# pinguino_p8b3_RC2.net
KiCad netlist of a schematic drawn in EAGLE
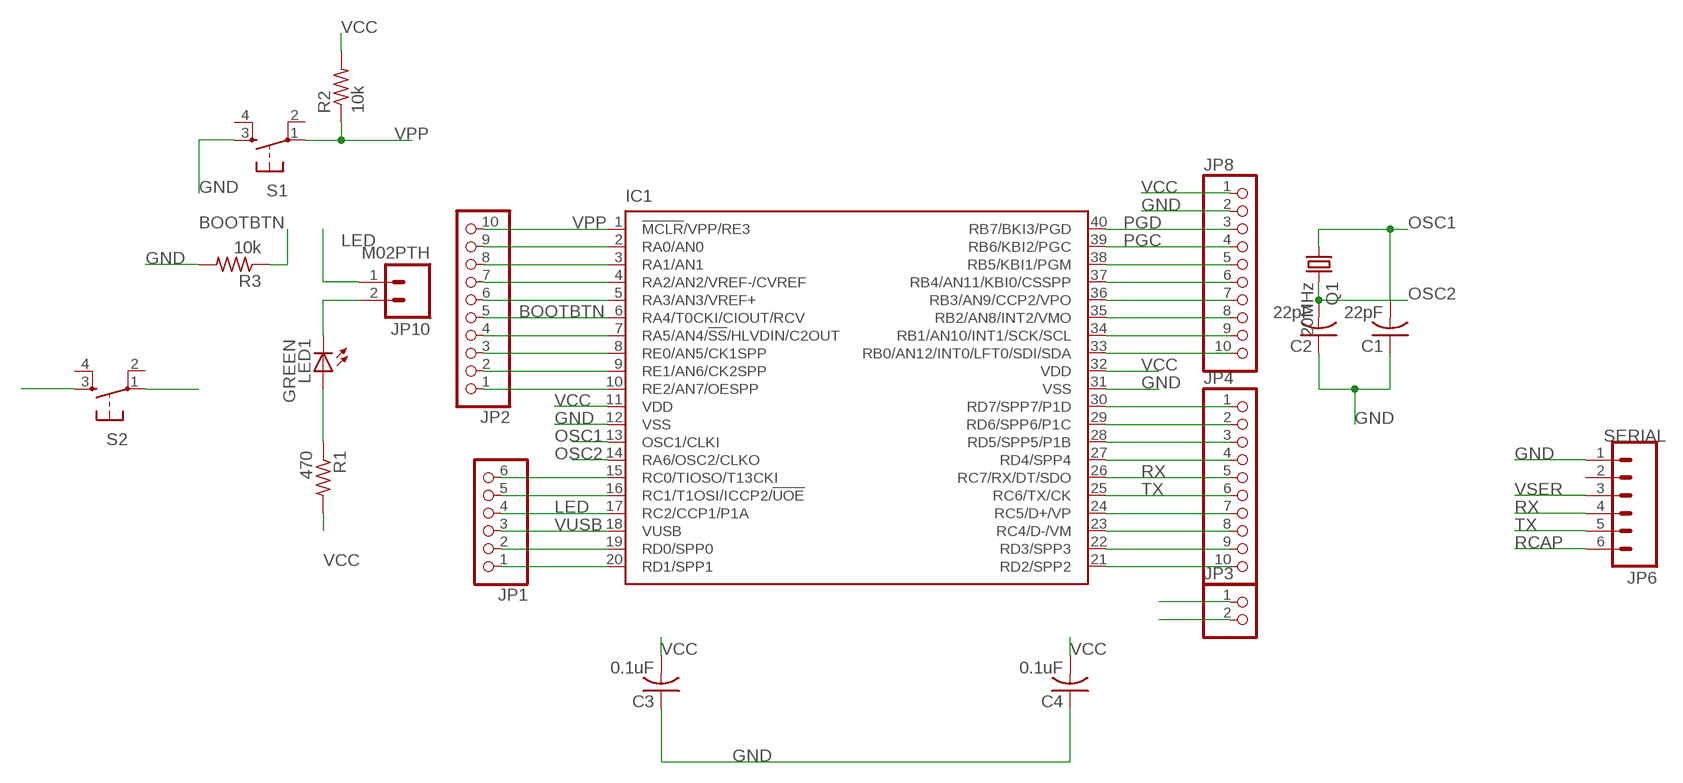
[diagram p0: schematic, sheet 1]

(export (version "E")
  (design (tool "Eeschema 10.0.6"))
  (components
    (comp (ref "C1")
      (value "22pF")
      (footprint "eagle-import:C025-025X050")
      (libsource (lib "eagle-import") (part "C-US025-025X050"))
    )
    (comp (ref "C2")
      (value "22pF")
      (footprint "eagle-import:C025-025X050")
      (libsource (lib "eagle-import") (part "C-US025-025X050"))
    )
    (comp (ref "C3")
      (value "0.1uF")
      (footprint "eagle-import:C025-025X050")
      (libsource (lib "eagle-import") (part "C-US025-025X050"))
    )
    (comp (ref "C4")
      (value "0.1uF")
      (footprint "eagle-import:C025-025X050")
      (libsource (lib "eagle-import") (part "C-US025-025X050"))
    )
    (comp (ref "IC1")
      (value "PIC18F4550_40")
      (footprint "eagle-import:DIL40")
      (libsource (lib "eagle-import") (part "PIC18F4_40550"))
    )
    (comp (ref "JP1")
      (value "PINHD-1X6")
      (footprint "eagle-import:1X06")
      (libsource (lib "eagle-import") (part "PINHD-1X6"))
    )
    (comp (ref "JP2")
      (value "PINHD-1X10")
      (footprint "eagle-import:1X10")
      (libsource (lib "eagle-import") (part "PINHD-1X10"))
    )
    (comp (ref "JP3")
      (value "PINHD-1X2")
      (footprint "eagle-import:1X02")
      (libsource (lib "eagle-import") (part "PINHD-1X2"))
    )
    (comp (ref "JP4")
      (value "PINHD-1X10")
      (footprint "eagle-import:1X10")
      (libsource (lib "eagle-import") (part "PINHD-1X10"))
    )
    (comp (ref "JP6")
      (value "M06SIP")
      (footprint "eagle-import:1X06")
      (libsource (lib "eagle-import") (part "M06SIP"))
    )
    (comp (ref "JP8")
      (value "PINHD-1X10")
      (footprint "eagle-import:1X10")
      (libsource (lib "eagle-import") (part "PINHD-1X10"))
    )
    (comp (ref "JP10")
      (value "M02PTH")
      (footprint "eagle-import:1X02")
      (libsource (lib "eagle-import") (part "M02PTH"))
    )
    (comp (ref "LED1")
      (value "GREEN")
      (footprint "eagle-import:LED3MM")
      (libsource (lib "eagle-import") (part "LED3MM"))
    )
    (comp (ref "Q1")
      (value "20MHz")
      (footprint "eagle-import:HC49US")
      (libsource (lib "eagle-import") (part "CRYSTALHC49US"))
    )
    (comp (ref "R1")
      (value "470")
      (footprint "eagle-import:0207_10")
      (libsource (lib "eagle-import") (part "R-US_0207/10"))
    )
    (comp (ref "R2")
      (value "10k")
      (footprint "eagle-import:0207_7")
      (libsource (lib "eagle-import") (part "R-US_0207/7"))
    )
    (comp (ref "R3")
      (value "10k")
      (footprint "eagle-import:0207_7")
      (libsource (lib "eagle-import") (part "R-US_0207/7"))
    )
    (comp (ref "S1")
      (value "TAC_SWITCHPTH")
      (footprint "eagle-import:TACTILE-PTH")
      (libsource (lib "eagle-import") (part "TAC_SWITCHPTH"))
    )
    (comp (ref "S2")
      (value "TAC_SWITCHPTH")
      (footprint "eagle-import:TACTILE-PTH")
      (libsource (lib "eagle-import") (part "TAC_SWITCHPTH"))
    )
  )
  (nets
    (net (code "1") (name "/BOOTBTN") (class "Default")
      (node (ref "IC1") (pin "6") (pinfunction "RA4/T0CKI/CIOUT/RCV_6") (pintype "bidirectional"))
      (node (ref "JP2") (pin "5") (pinfunction "5_5") (pintype "passive"))
      (node (ref "R3") (pin "1") (pinfunction "1_1") (pintype "passive"))
      (node (ref "S2") (pin "1") (pinfunction "1_1") (pintype "passive"))
    )
    (net (code "2") (name "/GND") (class "Default")
      (node (ref "C1") (pin "1") (pinfunction "1_1") (pintype "passive"))
      (node (ref "C2") (pin "1") (pinfunction "1_1") (pintype "passive"))
      (node (ref "C3") (pin "1") (pinfunction "1_1") (pintype "passive"))
      (node (ref "C4") (pin "1") (pinfunction "1_1") (pintype "passive"))
      (node (ref "IC1") (pin "12") (pinfunction "VSS_12") (pintype "power_in"))
      (node (ref "IC1") (pin "31") (pinfunction "VSS_31") (pintype "power_in"))
      (node (ref "JP6") (pin "1") (pinfunction "1_1") (pintype "passive"))
      (node (ref "JP8") (pin "2") (pinfunction "2_2") (pintype "passive"))
      (node (ref "R3") (pin "2") (pinfunction "2_2") (pintype "passive"))
      (node (ref "S1") (pin "3") (pinfunction "3_3") (pintype "passive"))
    )
    (net (code "3") (name "/LED") (class "Default")
      (node (ref "IC1") (pin "17") (pinfunction "RC2/CCP1/P1A_17") (pintype "bidirectional"))
      (node (ref "JP1") (pin "4") (pinfunction "4_4") (pintype "passive"))
      (node (ref "JP10") (pin "1") (pinfunction "1_1") (pintype "passive"))
    )
    (net (code "4") (name "/OSC1") (class "Default")
      (node (ref "C1") (pin "2") (pinfunction "2_2") (pintype "passive"))
      (node (ref "IC1") (pin "13") (pinfunction "OSC1/CLKI_13") (pintype "input"))
      (node (ref "Q1") (pin "1") (pinfunction "1_1") (pintype "passive"))
    )
    (net (code "5") (name "/OSC2") (class "Default")
      (node (ref "C2") (pin "2") (pinfunction "2_2") (pintype "passive"))
      (node (ref "IC1") (pin "14") (pinfunction "RA6/OSC2/CLKO_14") (pintype "output"))
      (node (ref "Q1") (pin "2") (pinfunction "2_2") (pintype "passive"))
    )
    (net (code "6") (name "/PGC") (class "Default")
      (node (ref "IC1") (pin "39") (pinfunction "RB6/KBI2/PGC_39") (pintype "bidirectional"))
      (node (ref "JP8") (pin "4") (pinfunction "4_4") (pintype "passive"))
    )
    (net (code "7") (name "/PGD") (class "Default")
      (node (ref "IC1") (pin "40") (pinfunction "RB7/BKI3/PGD_40") (pintype "bidirectional"))
      (node (ref "JP8") (pin "3") (pinfunction "3_3") (pintype "passive"))
    )
    (net (code "8") (name "/RCAP") (class "Default")
      (node (ref "JP6") (pin "6") (pinfunction "6_6") (pintype "passive"))
    )
    (net (code "9") (name "/RX") (class "Default")
      (node (ref "IC1") (pin "26") (pinfunction "RC7/RX/DT/SDO_26") (pintype "bidirectional"))
      (node (ref "JP4") (pin "5") (pinfunction "5_5") (pintype "passive"))
      (node (ref "JP6") (pin "4") (pinfunction "4_4") (pintype "passive"))
    )
    (net (code "10") (name "/TX") (class "Default")
      (node (ref "IC1") (pin "25") (pinfunction "RC6/TX/CK_25") (pintype "bidirectional"))
      (node (ref "JP4") (pin "6") (pinfunction "6_6") (pintype "passive"))
      (node (ref "JP6") (pin "5") (pinfunction "5_5") (pintype "passive"))
    )
    (net (code "11") (name "/VCC") (class "Default")
      (node (ref "C3") (pin "2") (pinfunction "2_2") (pintype "passive"))
      (node (ref "C4") (pin "2") (pinfunction "2_2") (pintype "passive"))
      (node (ref "IC1") (pin "11") (pinfunction "VDD_11") (pintype "power_in"))
      (node (ref "IC1") (pin "32") (pinfunction "VDD_32") (pintype "power_in"))
      (node (ref "JP3") (pin "1") (pinfunction "1_1") (pintype "passive"))
      (node (ref "JP8") (pin "1") (pinfunction "1_1") (pintype "passive"))
      (node (ref "R1") (pin "2") (pinfunction "2_2") (pintype "passive"))
      (node (ref "R2") (pin "2") (pinfunction "2_2") (pintype "passive"))
      (node (ref "S2") (pin "3") (pinfunction "3_3") (pintype "passive"))
    )
    (net (code "12") (name "/VPP") (class "Default")
      (node (ref "IC1") (pin "1") (pinfunction "~{MCLR}/VPP/RE3_1") (pintype "input"))
      (node (ref "JP2") (pin "10") (pinfunction "10_10") (pintype "passive"))
      (node (ref "R2") (pin "1") (pinfunction "1_1") (pintype "passive"))
      (node (ref "S1") (pin "1") (pinfunction "1_1") (pintype "passive"))
    )
    (net (code "13") (name "/VSER") (class "Default")
      (node (ref "JP3") (pin "2") (pinfunction "2_2") (pintype "passive"))
      (node (ref "JP6") (pin "3") (pinfunction "3_3") (pintype "passive"))
    )
    (net (code "14") (name "/VUSB") (class "Default")
      (node (ref "IC1") (pin "18") (pinfunction "VUSB_18") (pintype "bidirectional"))
      (node (ref "JP1") (pin "3") (pinfunction "3_3") (pintype "passive"))
    )
    (net (code "15") (name "Net-(IC1-RA0{slash}AN0)") (class "Default")
      (node (ref "IC1") (pin "2") (pinfunction "RA0/AN0_2") (pintype "bidirectional"))
      (node (ref "JP2") (pin "9") (pinfunction "9_9") (pintype "passive"))
    )
    (net (code "16") (name "Net-(IC1-RA1{slash}AN1)") (class "Default")
      (node (ref "IC1") (pin "3") (pinfunction "RA1/AN1_3") (pintype "bidirectional"))
      (node (ref "JP2") (pin "8") (pinfunction "8_8") (pintype "passive"))
    )
    (net (code "17") (name "Net-(IC1-RA2{slash}AN2{slash}VREF-{slash}CVREF)") (class "Default")
      (node (ref "IC1") (pin "4") (pinfunction "RA2/AN2/VREF-/CVREF_4") (pintype "bidirectional"))
      (node (ref "JP2") (pin "7") (pinfunction "7_7") (pintype "passive"))
    )
    (net (code "18") (name "Net-(IC1-RA3{slash}AN3{slash}VREF+)") (class "Default")
      (node (ref "IC1") (pin "5") (pinfunction "RA3/AN3/VREF+_5") (pintype "bidirectional"))
      (node (ref "JP2") (pin "6") (pinfunction "6_6") (pintype "passive"))
    )
    (net (code "19") (name "Net-(IC1-RA5{slash}AN4{slash}~{SS}{slash}HLVDIN{slash}C2OUT)") (class "Default")
      (node (ref "IC1") (pin "7") (pinfunction "RA5/AN4/~{SS}/HLVDIN/C2OUT_7") (pintype "bidirectional"))
      (node (ref "JP2") (pin "4") (pinfunction "4_4") (pintype "passive"))
    )
    (net (code "20") (name "Net-(IC1-RB0{slash}AN12{slash}INT0{slash}LFT0{slash}SDI{slash}SDA)") (class "Default")
      (node (ref "IC1") (pin "33") (pinfunction "RB0/AN12/INT0/LFT0/SDI/SDA_33") (pintype "bidirectional"))
      (node (ref "JP8") (pin "10") (pinfunction "10_10") (pintype "passive"))
    )
    (net (code "21") (name "Net-(IC1-RB1{slash}AN10{slash}INT1{slash}SCK{slash}SCL)") (class "Default")
      (node (ref "IC1") (pin "34") (pinfunction "RB1/AN10/INT1/SCK/SCL_34") (pintype "bidirectional"))
      (node (ref "JP8") (pin "9") (pinfunction "9_9") (pintype "passive"))
    )
    (net (code "22") (name "Net-(IC1-RB2{slash}AN8{slash}INT2{slash}VMO)") (class "Default")
      (node (ref "IC1") (pin "35") (pinfunction "RB2/AN8/INT2/VMO_35") (pintype "bidirectional"))
      (node (ref "JP8") (pin "8") (pinfunction "8_8") (pintype "passive"))
    )
    (net (code "23") (name "Net-(IC1-RB3{slash}AN9{slash}CCP2{slash}VPO)") (class "Default")
      (node (ref "IC1") (pin "36") (pinfunction "RB3/AN9/CCP2/VPO_36") (pintype "bidirectional"))
      (node (ref "JP8") (pin "7") (pinfunction "7_7") (pintype "passive"))
    )
    (net (code "24") (name "Net-(IC1-RB4{slash}AN11{slash}KBI0{slash}CSSPP)") (class "Default")
      (node (ref "IC1") (pin "37") (pinfunction "RB4/AN11/KBI0/CSSPP_37") (pintype "bidirectional"))
      (node (ref "JP8") (pin "6") (pinfunction "6_6") (pintype "passive"))
    )
    (net (code "25") (name "Net-(IC1-RB5{slash}KBI1{slash}PGM)") (class "Default")
      (node (ref "IC1") (pin "38") (pinfunction "RB5/KBI1/PGM_38") (pintype "bidirectional"))
      (node (ref "JP8") (pin "5") (pinfunction "5_5") (pintype "passive"))
    )
    (net (code "26") (name "Net-(IC1-RC0{slash}TIOSO{slash}T13CKI)") (class "Default")
      (node (ref "IC1") (pin "15") (pinfunction "RC0/TIOSO/T13CKI_15") (pintype "bidirectional"))
      (node (ref "JP1") (pin "6") (pinfunction "6_6") (pintype "passive"))
    )
    (net (code "27") (name "Net-(IC1-RC1{slash}T1OSI{slash}ICCP2{slash}~{UOE})") (class "Default")
      (node (ref "IC1") (pin "16") (pinfunction "RC1/T1OSI/ICCP2/~{UOE}_16") (pintype "bidirectional"))
      (node (ref "JP1") (pin "5") (pinfunction "5_5") (pintype "passive"))
    )
    (net (code "28") (name "Net-(IC1-RC4{slash}D-{slash}VM)") (class "Default")
      (node (ref "IC1") (pin "23") (pinfunction "RC4/D-/VM_23") (pintype "bidirectional"))
      (node (ref "JP4") (pin "8") (pinfunction "8_8") (pintype "passive"))
    )
    (net (code "29") (name "Net-(IC1-RC5{slash}D+{slash}VP)") (class "Default")
      (node (ref "IC1") (pin "24") (pinfunction "RC5/D+/VP_24") (pintype "bidirectional"))
      (node (ref "JP4") (pin "7") (pinfunction "7_7") (pintype "passive"))
    )
    (net (code "30") (name "Net-(IC1-RD0{slash}SPP0)") (class "Default")
      (node (ref "IC1") (pin "19") (pinfunction "RD0/SPP0_19") (pintype "bidirectional"))
      (node (ref "JP1") (pin "2") (pinfunction "2_2") (pintype "passive"))
    )
    (net (code "31") (name "Net-(IC1-RD1{slash}SPP1)") (class "Default")
      (node (ref "IC1") (pin "20") (pinfunction "RD1/SPP1_20") (pintype "bidirectional"))
      (node (ref "JP1") (pin "1") (pinfunction "1_1") (pintype "passive"))
    )
    (net (code "32") (name "Net-(IC1-RD2{slash}SPP2)") (class "Default")
      (node (ref "IC1") (pin "21") (pinfunction "RD2/SPP2_21") (pintype "bidirectional"))
      (node (ref "JP4") (pin "10") (pinfunction "10_10") (pintype "passive"))
    )
    (net (code "33") (name "Net-(IC1-RD3{slash}SPP3)") (class "Default")
      (node (ref "IC1") (pin "22") (pinfunction "RD3/SPP3_22") (pintype "bidirectional"))
      (node (ref "JP4") (pin "9") (pinfunction "9_9") (pintype "passive"))
    )
    (net (code "34") (name "Net-(IC1-RD4{slash}SPP4)") (class "Default")
      (node (ref "IC1") (pin "27") (pinfunction "RD4/SPP4_27") (pintype "bidirectional"))
      (node (ref "JP4") (pin "4") (pinfunction "4_4") (pintype "passive"))
    )
    (net (code "35") (name "Net-(IC1-RD5{slash}SPP5{slash}P1B)") (class "Default")
      (node (ref "IC1") (pin "28") (pinfunction "RD5/SPP5/P1B_28") (pintype "bidirectional"))
      (node (ref "JP4") (pin "3") (pinfunction "3_3") (pintype "passive"))
    )
    (net (code "36") (name "Net-(IC1-RD6{slash}SPP6{slash}P1C)") (class "Default")
      (node (ref "IC1") (pin "29") (pinfunction "RD6/SPP6/P1C_29") (pintype "bidirectional"))
      (node (ref "JP4") (pin "2") (pinfunction "2_2") (pintype "passive"))
    )
    (net (code "37") (name "Net-(IC1-RD7{slash}SPP7{slash}P1D)") (class "Default")
      (node (ref "IC1") (pin "30") (pinfunction "RD7/SPP7/P1D_30") (pintype "bidirectional"))
      (node (ref "JP4") (pin "1") (pinfunction "1_1") (pintype "passive"))
    )
    (net (code "38") (name "Net-(IC1-RE0{slash}AN5{slash}CK1SPP)") (class "Default")
      (node (ref "IC1") (pin "8") (pinfunction "RE0/AN5/CK1SPP_8") (pintype "bidirectional"))
      (node (ref "JP2") (pin "3") (pinfunction "3_3") (pintype "passive"))
    )
    (net (code "39") (name "Net-(IC1-RE1{slash}AN6{slash}CK2SPP)") (class "Default")
      (node (ref "IC1") (pin "9") (pinfunction "RE1/AN6/CK2SPP_9") (pintype "bidirectional"))
      (node (ref "JP2") (pin "2") (pinfunction "2_2") (pintype "passive"))
    )
    (net (code "40") (name "Net-(IC1-RE2{slash}AN7{slash}OESPP)") (class "Default")
      (node (ref "IC1") (pin "10") (pinfunction "RE2/AN7/OESPP_10") (pintype "bidirectional"))
      (node (ref "JP2") (pin "1") (pinfunction "1_1") (pintype "passive"))
    )
    (net (code "41") (name "Net-(LED1-C)") (class "Default")
      (node (ref "JP10") (pin "2") (pinfunction "2_2") (pintype "passive"))
      (node (ref "LED1") (pin "K") (pinfunction "C_K") (pintype "passive"))
    )
    (net (code "42") (name "Net-(LED1-PadA)") (class "Default")
      (node (ref "LED1") (pin "A") (pinfunction "A_A") (pintype "passive"))
      (node (ref "R1") (pin "1") (pinfunction "1_1") (pintype "passive"))
    )
    (net (code "43") (name "unconnected-(JP6-Pad2)") (class "Default")
      (node (ref "JP6") (pin "2") (pinfunction "2_2") (pintype "passive"))
    )
    (net (code "44") (name "unconnected-(S1-Pad2)") (class "Default")
      (node (ref "S1") (pin "2") (pinfunction "2_2") (pintype "passive"))
    )
    (net (code "45") (name "unconnected-(S1-Pad4)") (class "Default")
      (node (ref "S1") (pin "4") (pinfunction "4_4") (pintype "passive"))
    )
    (net (code "46") (name "unconnected-(S2-Pad2)") (class "Default")
      (node (ref "S2") (pin "2") (pinfunction "2_2") (pintype "passive"))
    )
    (net (code "47") (name "unconnected-(S2-Pad4)") (class "Default")
      (node (ref "S2") (pin "4") (pinfunction "4_4") (pintype "passive"))
    )
  )
)
